# Thunder-Refix.net
KiCad netlist of a schematic drawn in Altium Designer
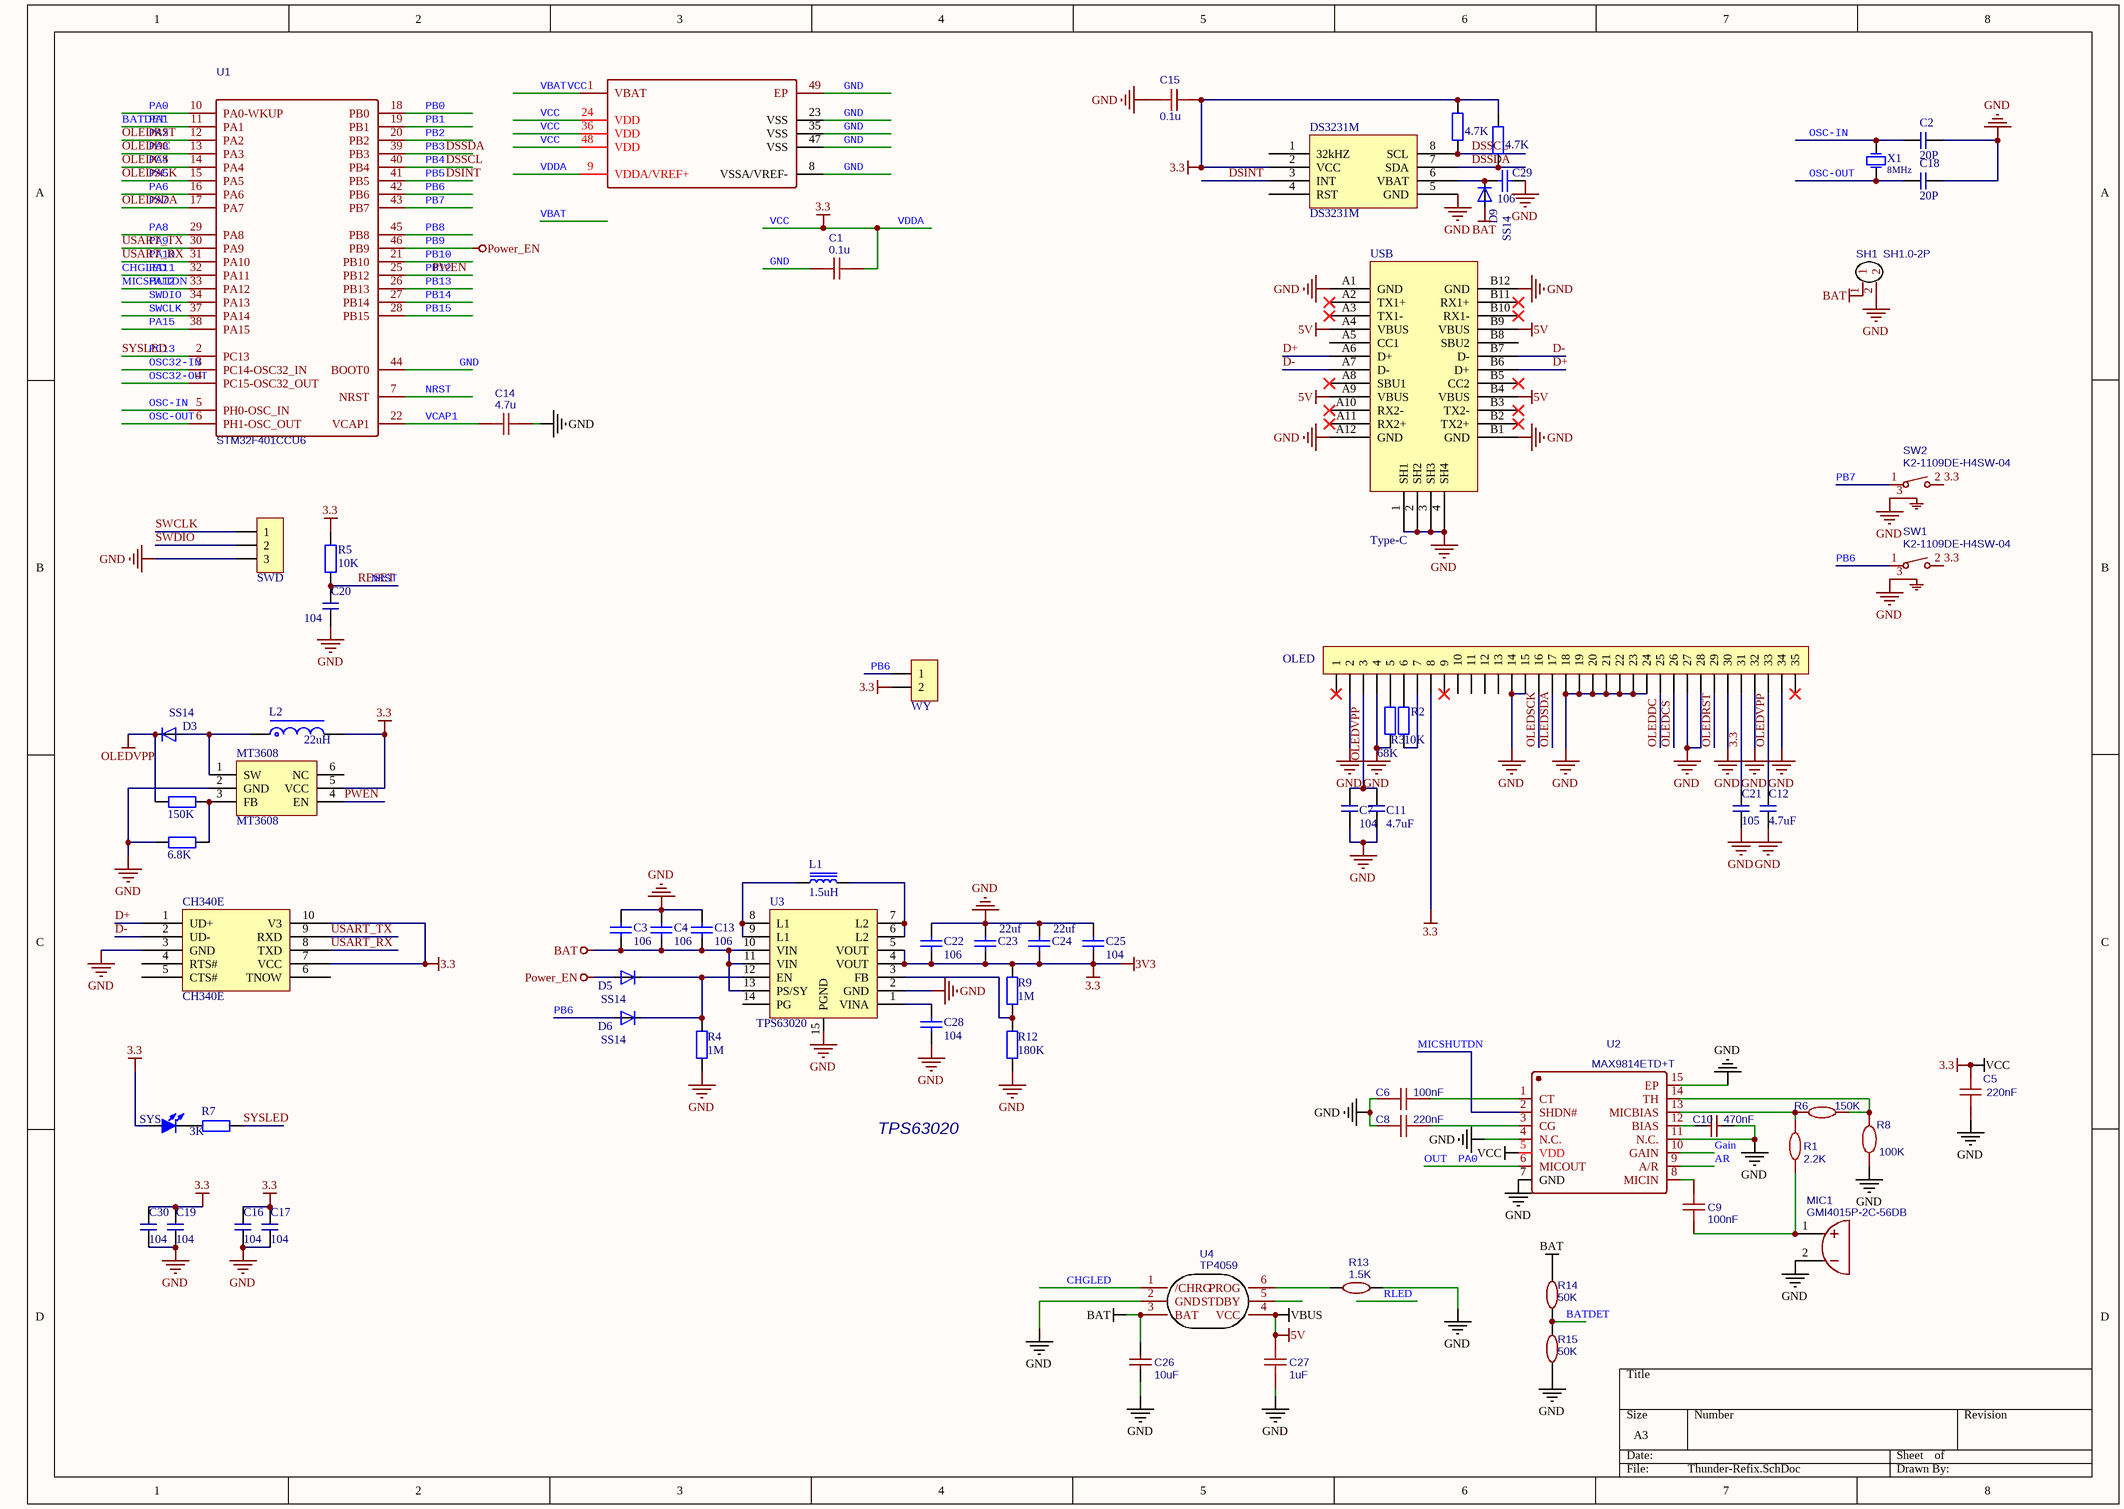
[diagram p0: Thunder-Refix.SchDoc]

(export (version "E")
  (design (tool "Eeschema 10.0.6"))
  (components
    (comp (ref "C1")
      (value "0.1u")
      (footprint "0603C")
      (fields (field (name "CONTRIBUTOR") "LCEDA_Lib"))
      (libsource (lib "altium-import") (part "root_2_0.1u_"))
    )
    (comp (ref "C2") (value "20P") (footprint "0603C") (libsource (lib "Schlib1") (part "电容")))
    (comp (ref "C3")
      (value "106")
      (footprint "我的PCB库:0603c")
      (fields (field (name "C") "106"))
      (libsource (lib "元件库") (part "cap"))
    )
    (comp (ref "C4")
      (value "106")
      (footprint "我的PCB库:0603c")
      (fields (field (name "C") "106"))
      (libsource (lib "元件库") (part "cap"))
    )
    (comp (ref "C5")
      (value "220nF")
      (footprint "0603c")
      (fields
        (field (name "BOM_SUPPLIER PART") "C354366")
        (field (name "BOM_MANUFACTURER PART") "GCJ21BR71H224KA01L")
        (field (name "CONTRIBUTOR") "LCSC")
      )
      (libsource (lib "altium-import") (part "root_1_220nF_"))
    )
    (comp (ref "C6")
      (value "100nF")
      (footprint "0603c")
      (fields
        (field (name "BOM_SUPPLIER PART") "C444732")
        (field (name "BOM_MANUFACTURER PART") "FS055C104K4Z2A")
        (field (name "CONTRIBUTOR") "LCSC")
      )
      (libsource (lib "altium-import") (part "root_1_100nF_"))
    )
    (comp (ref "C7") (value "104") (footprint "0603C") (libsource (lib "Schlib1") (part "电容")))
    (comp (ref "C8")
      (value "220nF")
      (footprint "0603c")
      (fields
        (field (name "BOM_SUPPLIER PART") "C354366")
        (field (name "BOM_MANUFACTURER PART") "GCJ21BR71H224KA01L")
        (field (name "CONTRIBUTOR") "LCSC")
      )
      (libsource (lib "altium-import") (part "root_0_220nF_"))
    )
    (comp (ref "C9")
      (value "100nF")
      (footprint "0603c")
      (fields
        (field (name "BOM_SUPPLIER PART") "C444732")
        (field (name "BOM_MANUFACTURER PART") "FS055C104K4Z2A")
        (field (name "CONTRIBUTOR") "LCSC")
      )
      (libsource (lib "altium-import") (part "root_0_100nF_"))
    )
    (comp (ref "C10")
      (value "470nF")
      (footprint "0603c")
      (fields
        (field (name "BOM_MANUFACTURER PART") "CL21B474KBFNNNE")
        (field (name "BOM_SUPPLIER PART") "C13967")
      )
      (libsource (lib "altium-import") (part "root_0_470nF_"))
    )
    (comp (ref "C11") (value "4.7uF") (footprint "0603C") (libsource (lib "Schlib1") (part "电容")))
    (comp (ref "C12") (value "4.7uF") (footprint "0603C") (libsource (lib "Schlib1") (part "电容")))
    (comp (ref "C13")
      (value "106")
      (footprint "0603c")
      (fields (field (name "C") "106"))
      (libsource (lib "元件库") (part "cap"))
    )
    (comp (ref "C14")
      (value "4.7u")
      (footprint "0603C")
      (fields (field (name "CONTRIBUTOR") "LCEDA_Lib"))
      (libsource (lib "altium-import") (part "root_0_4.7u_"))
    )
    (comp (ref "C15")
      (value "0.1u")
      (footprint "0603C")
      (fields (field (name "CONTRIBUTOR") "LCEDA_Lib"))
      (libsource (lib "altium-import") (part "root_2_0.1u_"))
    )
    (comp (ref "C16") (value "104") (footprint "0603C") (libsource (lib "Schlib1") (part "电容")))
    (comp (ref "C17") (value "104") (footprint "0603C") (libsource (lib "Schlib1") (part "电容")))
    (comp (ref "C18") (value "20P") (footprint "0603C") (libsource (lib "Schlib1") (part "电容")))
    (comp (ref "C19") (value "104") (footprint "0603C") (libsource (lib "Schlib1") (part "电容")))
    (comp (ref "C20") (value "104") (footprint "0603C") (libsource (lib "Schlib1") (part "电容")))
    (comp (ref "C21") (value "105") (footprint "0603C") (libsource (lib "Schlib1") (part "电容")))
    (comp (ref "C22")
      (value "106")
      (footprint "0603c")
      (fields (field (name "C") "106"))
      (libsource (lib "元件库") (part "cap"))
    )
    (comp (ref "C23")
      (value "22uf")
      (footprint "0603c")
      (fields (field (name "C") "22uf"))
      (libsource (lib "元件库") (part "cap"))
    )
    (comp (ref "C24")
      (value "22uf")
      (footprint "0603c")
      (fields (field (name "C") "22uf"))
      (libsource (lib "元件库") (part "cap"))
    )
    (comp (ref "C25")
      (value "104")
      (footprint "0603c")
      (fields (field (name "C") "104"))
      (libsource (lib "元件库") (part "cap"))
    )
    (comp (ref "C26")
      (value "10uF")
      (footprint "0603c")
      (fields
        (field (name "BOM_SUPPLIER PART") "C162317")
        (field (name "BOM_MANUFACTURER PART") "GRM21BB31C106KE15L")
        (field (name "CONTRIBUTOR") "LCSC")
      )
      (libsource (lib "altium-import") (part "root_1_10uF_"))
    )
    (comp (ref "C27")
      (value "1uF")
      (footprint "0603c")
      (fields
        (field (name "BOM_SUPPLIER PART") "C319195")
        (field (name "BOM_MANUFACTURER PART") "UMK212BJ105KG-T")
        (field (name "CONTRIBUTOR") "LCSC")
      )
      (libsource (lib "altium-import") (part "root_1_1uF_"))
    )
    (comp (ref "C28")
      (value "104")
      (footprint "0603c")
      (fields (field (name "C") "104"))
      (libsource (lib "元件库") (part "cap"))
    )
    (comp (ref "C29")
      (value "106")
      (footprint "0603c")
      (fields (field (name "C") "106"))
      (libsource (lib "元件库") (part "cap"))
    )
    (comp (ref "C30") (value "104") (footprint "0603C") (libsource (lib "Schlib1") (part "电容")))
    (comp (ref "CH340E") (value "CH340E") (footprint "MSOP10_L") (libsource (lib "CUBE_T1") (part "CH340E")))
    (comp (ref "D3")
      (value "SS14")
      (footprint "SOD323_1N4148WS")
      (description "Diode Switching 75V 0.3A 2-Pin SOD-323 T/R")
      (fields (field (name "MF") "ON Semiconductor") (field (name "MP") "1N4148WS"))
      (libsource (lib "1N4148WS") (part "1N4148WS"))
    )
    (comp (ref "D5")
      (value "SS14")
      (footprint "SOD323_1N4148WS")
      (description "Diode Switching 75V 0.3A 2-Pin SOD-323 T/R")
      (fields (field (name "MF") "ON Semiconductor") (field (name "MP") "1N4148WS"))
      (libsource (lib "1N4148WS") (part "1N4148WS"))
    )
    (comp (ref "D6")
      (value "SS14")
      (footprint "SOD323_1N4148WS")
      (description "Diode Switching 75V 0.3A 2-Pin SOD-323 T/R")
      (fields (field (name "MF") "ON Semiconductor") (field (name "MP") "1N4148WS"))
      (libsource (lib "1N4148WS") (part "1N4148WS"))
    )
    (comp (ref "D9")
      (value "SS14")
      (footprint "SOD323_1N4148WS")
      (description "Diode Switching 75V 0.3A 2-Pin SOD-323 T/R")
      (fields (field (name "MF") "ON Semiconductor") (field (name "MP") "1N4148WS"))
      (libsource (lib "1N4148WS") (part "1N4148WS"))
    )
    (comp (ref "DS3231M") (value "DS3231M") (footprint "SOP8") (libsource (lib "CUBE_T1") (part "DS3231M")))
    (comp (ref "L1")
      (value "1.5uH")
      (footprint "我的PCB库:IND-SMD_L3.0-W3.0_NR3010")
      (fields (field (name "_VALUE") "1.5uH"))
      (libsource (lib "元件库") (part "Inductor Iron 2"))
    )
    (comp (ref "L2")
      (value "22uH")
      (footprint "IND-SMD_L3.0-W3.0_NR3010")
      (description "功率屏蔽电感")
      (fields (field (name "版权归属") "源创客"))
      (libsource (lib "3.1   - 电阻-电容-电感") (part "L-CDRH"))
    )
    (comp (ref "MIC1")
      (value "GMI4015P-2C-56DB")
      (footprint "MIC-TH_BD4.0-P2.00-D0.4-L-FD")
      (fields
        (field (name "BOM_SUPPLIER PART") "C233299")
        (field (name "BOM_MANUFACTURER PART") "GMI4015P-2C-56db")
        (field (name "CONTRIBUTOR") "LCSC")
      )
      (libsource (lib "altium-import") (part "root_0_GMI4015P-2C-56DB_"))
    )
    (comp (ref "MT3608")
      (value "MT3608")
      (footprint "SOT23-6N")
      (description "可调升压芯片")
      (fields (field (name "版权归属") "源创客"))
      (libsource (lib "1.3   - 电源类芯片") (part "SX1308"))
    )
    (comp (ref "OLED")
      (value "FPC1.0-35P")
      (footprint "1.69 OLED")
      (description "FPC连接器")
      (fields (field (name "版权归属") "源创客"))
      (libsource (lib "4.14 - FPC连接器") (part "FPC-35P"))
    )
    (comp (ref "R1")
      (value "2.2K")
      (footprint "0603r")
      (fields
        (field (name "BOM_SUPPLIER PART") "C325769")
        (field (name "BOM_MANUFACTURER PART") "RMC08052.2K1%N")
        (field (name "CONTRIBUTOR") "LCSC")
      )
      (libsource (lib "altium-import") (part "root_1_2.2K_"))
    )
    (comp (ref "R2")
      (value "10K")
      (footprint "0603R")
      (description "贴片电阻")
      (fields (field (name "版权归属") "源创客"))
      (libsource (lib "3.1   - 电阻-电容-电感") (part "R"))
    )
    (comp (ref "R3")
      (value "68K")
      (footprint "0603R")
      (description "贴片电阻")
      (fields (field (name "版权归属") "源创客"))
      (libsource (lib "3.1   - 电阻-电容-电感") (part "R"))
    )
    (comp (ref "R4")
      (value "1M")
      (footprint "0603r")
      (fields (field (name "R") "1M"))
      (libsource (lib "元件库") (part "Res"))
    )
    (comp (ref "R5")
      (value "10K")
      (footprint "0603R")
      (description "贴片电阻")
      (fields (field (name "版权归属") "源创客"))
      (libsource (lib "3.1   - 电阻-电容-电感") (part "R"))
    )
    (comp (ref "R6")
      (value "150K")
      (footprint "0603r")
      (fields
        (field (name "BOM_SUPPLIER PART") "C325765")
        (field (name "BOM_MANUFACTURER PART") "RMC0805150K1%N")
        (field (name "CONTRIBUTOR") "LCSC")
      )
      (libsource (lib "altium-import") (part "root_0_150K_"))
    )
    (comp (ref "R7")
      (value "3K")
      (footprint "0603R")
      (description "贴片电阻")
      (fields (field (name "版权归属") "源创客"))
      (libsource (lib "3.1   - 电阻-电容-电感") (part "R"))
    )
    (comp (ref "R8")
      (value "100K")
      (footprint "0603r")
      (fields
        (field (name "BOM_SUPPLIER PART") "C346756")
        (field (name "BOM_MANUFACTURER PART") "RTAN0805BKE100K")
        (field (name "CONTRIBUTOR") "LCSC")
      )
      (libsource (lib "altium-import") (part "root_1_100K_"))
    )
    (comp (ref "R9")
      (value "1M")
      (footprint "0603r")
      (fields (field (name "R") "1M"))
      (libsource (lib "元件库") (part "Res"))
    )
    (comp (ref "R10")
      (value "4.7K")
      (footprint "0603R")
      (description "贴片电阻")
      (fields (field (name "版权归属") "源创客"))
      (libsource (lib "3.1   - 电阻-电容-电感") (part "R"))
    )
    (comp (ref "R11")
      (value "4.7K")
      (footprint "0603R")
      (description "贴片电阻")
      (fields (field (name "版权归属") "源创客"))
      (libsource (lib "3.1   - 电阻-电容-电感") (part "R"))
    )
    (comp (ref "R12")
      (value "180K")
      (footprint "0603r")
      (fields (field (name "R") "180K"))
      (libsource (lib "元件库") (part "Res"))
    )
    (comp (ref "R13")
      (value "1.5K")
      (footprint "0603r")
      (fields
        (field (name "BOM_MANUFACTURER PART") "RC0603FR-071K5L")
        (field (name "BOM_SUPPLIER PART") "C114668")
      )
      (libsource (lib "altium-import") (part "root_0_1.5K_"))
    )
    (comp (ref "R14")
      (value "50K")
      (footprint "0603r")
      (fields
        (field (name "BOM_MANUFACTURER PART") "RC0603FR-071K5L")
        (field (name "BOM_SUPPLIER PART") "C114668")
      )
      (libsource (lib "altium-import") (part "root_1_1.5K_"))
    )
    (comp (ref "R15")
      (value "50K")
      (footprint "0603r")
      (fields
        (field (name "BOM_MANUFACTURER PART") "RC0603FR-071K5L")
        (field (name "BOM_SUPPLIER PART") "C114668")
      )
      (libsource (lib "altium-import") (part "root_1_1.5K_"))
    )
    (comp (ref "RB")
      (value "150K")
      (footprint "0603R")
      (description "贴片电阻")
      (fields (field (name "版权归属") "源创客"))
      (libsource (lib "3.1   - 电阻-电容-电感") (part "R"))
    )
    (comp (ref "RS")
      (value "6.8K")
      (footprint "0603R")
      (description "贴片电阻")
      (fields (field (name "版权归属") "源创客"))
      (libsource (lib "3.1   - 电阻-电容-电感") (part "R"))
    )
    (comp (ref "SH1")
      (value "SH1.0-2P")
      (footprint "SH1.0-2P")
      (fields (field (name "CONTRIBUTOR") "perry2867"))
      (libsource (lib "altium-import") (part "root_1_SH1.0-2P_"))
    )
    (comp (ref "SW1")
      (value "K2-1109DE-H4SW-04")
      (footprint "KEY-TH_K2-1109DE-CXXW-XX")
      (fields (field (name "BOM_SUPPLIER PART") "C961730") (field (name "CONTRIBUTOR") "LCSC"))
      (libsource (lib "altium-import") (part "root_0_K2-1109DE-H4SW-04_"))
    )
    (comp (ref "SW2")
      (value "K2-1109DE-H4SW-04")
      (footprint "KEY-TH_K2-1109DE-CXXW-XX")
      (fields (field (name "BOM_SUPPLIER PART") "C961730") (field (name "CONTRIBUTOR") "LCSC"))
      (libsource (lib "altium-import") (part "root_0_K2-1109DE-H4SW-04_"))
    )
    (comp (ref "SWD")
      (value "HDR-1X3")
      (footprint "ZH1.5-LI-3P")
      (description "3P接插件")
      (fields (field (name "版权归属") "源创客"))
      (libsource (lib "4.3   - 接插件-脚距1.5") (part "Header 3"))
    )
    (comp (ref "SYS")
      (value "粉色")
      (footprint "0603LED")
      (description "方形LED")
      (fields (field (name "版权归属") "源创客"))
      (libsource (lib "9.1   - LED") (part "LED-F234"))
    )
    (comp (ref "U1")
      (value "STM32F401CCU6")
      (footprint "QFN48 7X7_N")
      (fields (field (name "BOM_SUPPLIER PART") "C79861") (field (name "SUBPART_NO") "1"))
      (libsource (lib "Galaxy") (part "STM32F401CCU6"))
    )
    (comp (ref "U2")
      (value "MAX9814ETD+T")
      (footprint "TDFN-14_L3.0-W3.0-P0.40-BL-EP")
      (fields (field (name "BOM_SUPPLIER PART") "C41714"))
      (libsource (lib "altium-import") (part "root_0_MAX9814ETD+T_"))
    )
    (comp (ref "U3")
      (value "TPS63020")
      (footprint "我的PCB库:TPS63020")
      (libsource (lib "我的元件库") (part "TPS63020"))
    )
    (comp (ref "U4")
      (value "TP4059")
      (footprint "SOT23-6N")
      (fields (field (name "BOM_SUPPLIER PART") "C80364"))
      (libsource (lib "altium-import") (part "root_0_TP4059_"))
    )
    (comp (ref "USB") (value "Type-C") (footprint "Type-C") (libsource (lib "元件") (part "Type-C")))
    (comp (ref "WY")
      (value "HDR-1X2")
      (footprint "MX 1.25-WI-2P")
      (description "2P接插件")
      (fields (field (name "版权归属") "源创客"))
      (libsource (lib "4.2   - 接插件-脚距1.25") (part "Header 2"))
    )
    (comp (ref "X1")
      (value "8MHz")
      (footprint "OSC 5032-2P")
      (description "XTAL,8MHz,±20PPM,12.6*4.5")
      (fields (field (name "Comment") "1.6.1.01.005.001"))
      (libsource (lib "Mark_7") (part "1.6.1.01.005.001"))
    )
  )
  (nets
    (net (code "1") (name "/AR") (class "Default")
      (node (ref "U2") (pin "9") (pinfunction "A/R_9") (pintype "passive"))
    )
    (net (code "2") (name "/BATDET") (class "Default")
      (node (ref "R14") (pin "1") (pinfunction "1_1") (pintype "passive"))
      (node (ref "R15") (pin "2") (pinfunction "2_2") (pintype "passive"))
      (node (ref "U1") (pin "11") (pinfunction "PA1_11") (pintype "passive"))
    )
    (net (code "3") (name "/CHGLED") (class "Default")
      (node (ref "U1") (pin "32") (pinfunction "PA11_32") (pintype "passive"))
      (node (ref "U4") (pin "1") (pinfunction "/CHRG_1") (pintype "passive"))
    )
    (net (code "4") (name "/D+") (class "Default")
      (node (ref "CH340E") (pin "1") (pinfunction "UD+_1") (pintype "passive"))
      (node (ref "USB") (pin "A6") (pinfunction "D+_A6") (pintype "passive"))
      (node (ref "USB") (pin "B6") (pinfunction "D+_B6") (pintype "passive"))
    )
    (net (code "5") (name "/D-") (class "Default")
      (node (ref "CH340E") (pin "2") (pinfunction "UD-_2") (pintype "passive"))
      (node (ref "USB") (pin "A7") (pinfunction "D-_A7") (pintype "passive"))
      (node (ref "USB") (pin "B7") (pinfunction "D-_B7") (pintype "passive"))
    )
    (net (code "6") (name "/DSINT") (class "Default")
      (node (ref "DS3231M") (pin "3") (pinfunction "INT_3") (pintype "passive"))
      (node (ref "U1") (pin "41") (pinfunction "PB5_41") (pintype "passive"))
    )
    (net (code "7") (name "/DSSCL") (class "Default")
      (node (ref "DS3231M") (pin "8") (pinfunction "SCL_8") (pintype "passive"))
      (node (ref "R10") (pin "2") (pinfunction "2_2") (pintype "passive"))
      (node (ref "U1") (pin "40") (pinfunction "PB4_40") (pintype "passive"))
    )
    (net (code "8") (name "/DSSDA") (class "Default")
      (node (ref "DS3231M") (pin "7") (pinfunction "SDA_7") (pintype "passive"))
      (node (ref "R11") (pin "2") (pinfunction "2_2") (pintype "passive"))
      (node (ref "U1") (pin "39") (pinfunction "PB3_39") (pintype "passive"))
    )
    (net (code "9") (name "/Gain") (class "Default")
      (node (ref "U2") (pin "10") (pinfunction "GAIN_10") (pintype "passive"))
    )
    (net (code "10") (name "/MICSHUTDN") (class "Default")
      (node (ref "U1") (pin "33") (pinfunction "PA12_33") (pintype "passive"))
      (node (ref "U2") (pin "2") (pinfunction "SHDN#_2") (pintype "passive"))
    )
    (net (code "11") (name "/NRST") (class "Default")
      (node (ref "C20") (pin "1") (pinfunction "1_1") (pintype "passive"))
      (node (ref "R5") (pin "2") (pinfunction "2_2") (pintype "passive"))
      (node (ref "U1") (pin "7") (pinfunction "NRST_7") (pintype "passive"))
    )
    (net (code "12") (name "/OLEDCS") (class "Default")
      (node (ref "OLED") (pin "26") (pinfunction "26_26") (pintype "passive"))
      (node (ref "U1") (pin "14") (pinfunction "PA4_14") (pintype "passive"))
    )
    (net (code "13") (name "/OLEDDC") (class "Default")
      (node (ref "OLED") (pin "25") (pinfunction "25_25") (pintype "passive"))
      (node (ref "U1") (pin "13") (pinfunction "PA3_13") (pintype "passive"))
    )
    (net (code "14") (name "/OLEDRST") (class "Default")
      (node (ref "OLED") (pin "29") (pinfunction "29_29") (pintype "passive"))
      (node (ref "U1") (pin "12") (pinfunction "PA2_12") (pintype "passive"))
    )
    (net (code "15") (name "/OLEDSCK") (class "Default")
      (node (ref "OLED") (pin "16") (pinfunction "16_16") (pintype "passive"))
      (node (ref "U1") (pin "15") (pinfunction "PA5_15") (pintype "passive"))
    )
    (net (code "16") (name "/OLEDSDA") (class "Default")
      (node (ref "OLED") (pin "17") (pinfunction "17_17") (pintype "passive"))
      (node (ref "U1") (pin "17") (pinfunction "PA7_17") (pintype "passive"))
    )
    (net (code "17") (name "/OSC-IN") (class "Default")
      (node (ref "C2") (pin "2") (pinfunction "2_2") (pintype "passive"))
      (node (ref "U1") (pin "5") (pinfunction "PH0-OSC_IN_5") (pintype "passive"))
      (node (ref "X1") (pin "1") (pinfunction "OSC1_1") (pintype "passive"))
    )
    (net (code "18") (name "/OSC-OUT") (class "Default")
      (node (ref "C18") (pin "2") (pinfunction "2_2") (pintype "passive"))
      (node (ref "U1") (pin "6") (pinfunction "PH1-OSC_OUT_6") (pintype "passive"))
      (node (ref "X1") (pin "2") (pinfunction "OSC2_2") (pintype "passive"))
    )
    (net (code "19") (name "/OSC32-IN") (class "Default")
      (node (ref "U1") (pin "3") (pinfunction "PC14-OSC32_IN_3") (pintype "passive"))
    )
    (net (code "20") (name "/OSC32-OUT") (class "Default")
      (node (ref "U1") (pin "4") (pinfunction "PC15-OSC32_OUT_4") (pintype "passive"))
    )
    (net (code "21") (name "/OUT") (class "Default")
      (node (ref "U1") (pin "10") (pinfunction "PA0-WKUP_10") (pintype "passive"))
      (node (ref "U2") (pin "6") (pinfunction "MICOUT_6") (pintype "passive"))
    )
    (net (code "22") (name "/PA6") (class "Default")
      (node (ref "U1") (pin "16") (pinfunction "PA6_16") (pintype "passive"))
    )
    (net (code "23") (name "/PA8") (class "Default")
      (node (ref "U1") (pin "29") (pinfunction "PA8_29") (pintype "passive"))
    )
    (net (code "24") (name "/PA9") (class "Default")
      (node (ref "CH340E") (pin "9") (pinfunction "RXD_9") (pintype "passive"))
      (node (ref "U1") (pin "30") (pinfunction "PA9_30") (pintype "passive"))
    )
    (net (code "25") (name "/PA10") (class "Default")
      (node (ref "CH340E") (pin "8") (pinfunction "TXD_8") (pintype "passive"))
      (node (ref "U1") (pin "31") (pinfunction "PA10_31") (pintype "passive"))
    )
    (net (code "26") (name "/PA15") (class "Default")
      (node (ref "U1") (pin "38") (pinfunction "PA15_38") (pintype "passive"))
    )
    (net (code "27") (name "/PB0") (class "Default")
      (node (ref "U1") (pin "18") (pinfunction "PB0_18") (pintype "passive"))
    )
    (net (code "28") (name "/PB1") (class "Default")
      (node (ref "U1") (pin "19") (pinfunction "PB1_19") (pintype "passive"))
    )
    (net (code "29") (name "/PB2") (class "Default")
      (node (ref "U1") (pin "20") (pinfunction "PB2_20") (pintype "passive"))
    )
    (net (code "30") (name "/PB6") (class "Default")
      (node (ref "D6") (pin "A") (pinfunction "A_A") (pintype "passive"))
      (node (ref "SW1") (pin "1") (pinfunction "1_1") (pintype "passive"))
      (node (ref "U1") (pin "42") (pinfunction "PB6_42") (pintype "passive"))
      (node (ref "WY") (pin "1") (pinfunction "1_1") (pintype "passive"))
    )
    (net (code "31") (name "/PB7") (class "Default")
      (node (ref "SW2") (pin "1") (pinfunction "1_1") (pintype "passive"))
      (node (ref "U1") (pin "43") (pinfunction "PB7_43") (pintype "passive"))
    )
    (net (code "32") (name "/PB8") (class "Default")
      (node (ref "U1") (pin "45") (pinfunction "PB8_45") (pintype "passive"))
    )
    (net (code "33") (name "/PB10") (class "Default")
      (node (ref "U1") (pin "21") (pinfunction "PB10_21") (pintype "passive"))
    )
    (net (code "34") (name "/PB12") (class "Default")
      (node (ref "MT3608") (pin "4") (pinfunction "EN_4") (pintype "passive"))
      (node (ref "U1") (pin "25") (pinfunction "PB12_25") (pintype "passive"))
    )
    (net (code "35") (name "/PB13") (class "Default")
      (node (ref "U1") (pin "26") (pinfunction "PB13_26") (pintype "passive"))
    )
    (net (code "36") (name "/PB14") (class "Default")
      (node (ref "U1") (pin "27") (pinfunction "PB14_27") (pintype "passive"))
    )
    (net (code "37") (name "/PB15") (class "Default")
      (node (ref "U1") (pin "28") (pinfunction "PB15_28") (pintype "passive"))
    )
    (net (code "38") (name "/PC13") (class "Default")
      (node (ref "R7") (pin "1") (pinfunction "1_1") (pintype "passive"))
      (node (ref "U1") (pin "2") (pinfunction "PC13_2") (pintype "passive"))
    )
    (net (code "40") (name "/SWCLK") (class "Default")
      (node (ref "SWD") (pin "1") (pinfunction "1_1") (pintype "passive"))
      (node (ref "U1") (pin "37") (pinfunction "PA14_37") (pintype "passive"))
    )
    (net (code "41") (name "/SWDIO") (class "Default")
      (node (ref "SWD") (pin "2") (pinfunction "2_2") (pintype "passive"))
      (node (ref "U1") (pin "34") (pinfunction "PA13_34") (pintype "passive"))
    )
    (net (code "42") (name "/VCAP1") (class "Default")
      (node (ref "C14") (pin "1") (pinfunction "1_1") (pintype "passive"))
      (node (ref "U1") (pin "22") (pinfunction "VCAP1_22") (pintype "passive"))
    )
    (net (code "43") (name "3.3") (class "Default")
      (node (ref "C1") (pin "1") (pinfunction "1_1") (pintype "passive"))
      (node (ref "C15") (pin "1") (pinfunction "1_1") (pintype "passive"))
      (node (ref "C16") (pin "1") (pinfunction "1_1") (pintype "passive"))
      (node (ref "C17") (pin "1") (pinfunction "1_1") (pintype "passive"))
      (node (ref "C19") (pin "1") (pinfunction "1_1") (pintype "passive"))
      (node (ref "C21") (pin "1") (pinfunction "1_1") (pintype "passive"))
      (node (ref "C22") (pin "1") (pinfunction "1_1") (pintype "passive"))
      (node (ref "C23") (pin "1") (pinfunction "1_1") (pintype "passive"))
      (node (ref "C24") (pin "1") (pinfunction "1_1") (pintype "passive"))
      (node (ref "C25") (pin "1") (pinfunction "1_1") (pintype "passive"))
      (node (ref "C30") (pin "1") (pinfunction "1_1") (pintype "passive"))
      (node (ref "C5") (pin "2") (pinfunction "2_2") (pintype "passive"))
      (node (ref "CH340E") (pin "10") (pinfunction "V3_10") (pintype "passive"))
      (node (ref "CH340E") (pin "7") (pinfunction "VCC_7") (pintype "passive"))
      (node (ref "DS3231M") (pin "2") (pinfunction "VCC_2") (pintype "passive"))
      (node (ref "L2") (pin "2") (pinfunction "2_2") (pintype "passive"))
      (node (ref "MT3608") (pin "5") (pinfunction "VCC_5") (pintype "passive"))
      (node (ref "OLED") (pin "31") (pinfunction "31_31") (pintype "passive"))
      (node (ref "OLED") (pin "8") (pinfunction "8_8") (pintype "passive"))
      (node (ref "R10") (pin "1") (pinfunction "1_1") (pintype "passive"))
      (node (ref "R11") (pin "1") (pinfunction "1_1") (pintype "passive"))
      (node (ref "R5") (pin "1") (pinfunction "1_1") (pintype "passive"))
      (node (ref "R9") (pin "1") (pinfunction "1_1") (pintype "passive"))
      (node (ref "SW1") (pin "2") (pinfunction "2_2") (pintype "passive"))
      (node (ref "SW2") (pin "2") (pinfunction "2_2") (pintype "passive"))
      (node (ref "SYS") (pin "1") (pinfunction "A_1") (pintype "passive"))
      (node (ref "U1") (pin "1") (pinfunction "VBAT_1") (pintype "passive"))
      (node (ref "U1") (pin "24") (pinfunction "VDD_24") (pintype "passive"))
      (node (ref "U1") (pin "36") (pinfunction "VDD_36") (pintype "passive"))
      (node (ref "U1") (pin "48") (pinfunction "VDD_48") (pintype "passive"))
      (node (ref "U1") (pin "9") (pinfunction "VDDA/VREF+_9") (pintype "passive"))
      (node (ref "U2") (pin "5") (pinfunction "VDD_5") (pintype "passive"))
      (node (ref "U3") (pin "4") (pinfunction "VOUT_4") (pintype "passive"))
      (node (ref "U3") (pin "5") (pinfunction "VOUT_5") (pintype "passive"))
      (node (ref "WY") (pin "2") (pinfunction "2_2") (pintype "passive"))
    )
    (net (code "44") (name "5V") (class "Default")
      (node (ref "C27") (pin "1") (pinfunction "1_1") (pintype "passive"))
      (node (ref "U4") (pin "4") (pinfunction "VCC_4") (pintype "passive"))
      (node (ref "USB") (pin "A4") (pinfunction "VBUS_A4") (pintype "passive"))
      (node (ref "USB") (pin "A9") (pinfunction "VBUS_A9") (pintype "passive"))
      (node (ref "USB") (pin "B4") (pinfunction "VBUS_B4") (pintype "passive"))
      (node (ref "USB") (pin "B9") (pinfunction "VBUS_B9") (pintype "passive"))
    )
    (net (code "45") (name "BAT") (class "Default")
      (node (ref "C13") (pin "1") (pinfunction "1_1") (pintype "passive"))
      (node (ref "C26") (pin "2") (pinfunction "2_2") (pintype "passive"))
      (node (ref "C3") (pin "1") (pinfunction "1_1") (pintype "passive"))
      (node (ref "C4") (pin "1") (pinfunction "1_1") (pintype "passive"))
      (node (ref "D9") (pin "A") (pinfunction "A_A") (pintype "passive"))
      (node (ref "R14") (pin "2") (pinfunction "2_2") (pintype "passive"))
      (node (ref "SH1") (pin "1") (pinfunction "1_1") (pintype "passive"))
      (node (ref "U3") (pin "10") (pinfunction "VIN_10") (pintype "passive"))
      (node (ref "U3") (pin "11") (pinfunction "VIN_11") (pintype "passive"))
      (node (ref "U3") (pin "13") (pinfunction "PS/SY_13") (pintype "passive"))
      (node (ref "U4") (pin "3") (pinfunction "BAT_3") (pintype "passive"))
    )
    (net (code "46") (name "GND") (class "Default")
      (node (ref "C1") (pin "2") (pinfunction "2_2") (pintype "passive"))
      (node (ref "C10") (pin "2") (pinfunction "2_2") (pintype "passive"))
      (node (ref "C11") (pin "2") (pinfunction "2_2") (pintype "passive"))
      (node (ref "C12") (pin "2") (pinfunction "2_2") (pintype "passive"))
      (node (ref "C13") (pin "2") (pinfunction "2_2") (pintype "passive"))
      (node (ref "C14") (pin "2") (pinfunction "2_2") (pintype "passive"))
      (node (ref "C15") (pin "2") (pinfunction "2_2") (pintype "passive"))
      (node (ref "C16") (pin "2") (pinfunction "2_2") (pintype "passive"))
      (node (ref "C17") (pin "2") (pinfunction "2_2") (pintype "passive"))
      (node (ref "C18") (pin "1") (pinfunction "1_1") (pintype "passive"))
      (node (ref "C19") (pin "2") (pinfunction "2_2") (pintype "passive"))
      (node (ref "C2") (pin "1") (pinfunction "1_1") (pintype "passive"))
      (node (ref "C20") (pin "2") (pinfunction "2_2") (pintype "passive"))
      (node (ref "C21") (pin "2") (pinfunction "2_2") (pintype "passive"))
      (node (ref "C22") (pin "2") (pinfunction "2_2") (pintype "passive"))
      (node (ref "C23") (pin "2") (pinfunction "2_2") (pintype "passive"))
      (node (ref "C24") (pin "2") (pinfunction "2_2") (pintype "passive"))
      (node (ref "C25") (pin "2") (pinfunction "2_2") (pintype "passive"))
      (node (ref "C26") (pin "1") (pinfunction "1_1") (pintype "passive"))
      (node (ref "C27") (pin "2") (pinfunction "2_2") (pintype "passive"))
      (node (ref "C28") (pin "1") (pinfunction "1_1") (pintype "passive"))
      (node (ref "C29") (pin "1") (pinfunction "1_1") (pintype "passive"))
      (node (ref "C3") (pin "2") (pinfunction "2_2") (pintype "passive"))
      (node (ref "C30") (pin "2") (pinfunction "2_2") (pintype "passive"))
      (node (ref "C4") (pin "2") (pinfunction "2_2") (pintype "passive"))
      (node (ref "C5") (pin "1") (pinfunction "1_1") (pintype "passive"))
      (node (ref "C6") (pin "1") (pinfunction "1_1") (pintype "passive"))
      (node (ref "C7") (pin "2") (pinfunction "2_2") (pintype "passive"))
      (node (ref "C8") (pin "1") (pinfunction "1_1") (pintype "passive"))
      (node (ref "CH340E") (pin "3") (pinfunction "GND_3") (pintype "passive"))
      (node (ref "DS3231M") (pin "5") (pinfunction "GND_5") (pintype "passive"))
      (node (ref "MIC1") (pin "2") (pinfunction "2_2") (pintype "passive"))
      (node (ref "MT3608") (pin "2") (pinfunction "GND_2") (pintype "passive"))
      (node (ref "OLED") (pin "14") (pinfunction "14_14") (pintype "passive"))
      (node (ref "OLED") (pin "15") (pinfunction "15_15") (pintype "passive"))
      (node (ref "OLED") (pin "18") (pinfunction "18_18") (pintype "passive"))
      (node (ref "OLED") (pin "19") (pinfunction "19_19") (pintype "passive"))
      (node (ref "OLED") (pin "2") (pinfunction "2_2") (pintype "passive"))
      (node (ref "OLED") (pin "20") (pinfunction "20_20") (pintype "passive"))
      (node (ref "OLED") (pin "21") (pinfunction "21_21") (pintype "passive"))
      (node (ref "OLED") (pin "22") (pinfunction "22_22") (pintype "passive"))
      (node (ref "OLED") (pin "23") (pinfunction "23_23") (pintype "passive"))
      (node (ref "OLED") (pin "24") (pinfunction "24_24") (pintype "passive"))
      (node (ref "OLED") (pin "27") (pinfunction "27_27") (pintype "passive"))
      (node (ref "OLED") (pin "28") (pinfunction "28_28") (pintype "passive"))
      (node (ref "OLED") (pin "30") (pinfunction "30_30") (pintype "passive"))
      (node (ref "OLED") (pin "32") (pinfunction "32_32") (pintype "passive"))
      (node (ref "OLED") (pin "34") (pinfunction "34_34") (pintype "passive"))
      (node (ref "OLED") (pin "4") (pinfunction "4_4") (pintype "passive"))
      (node (ref "R12") (pin "2") (pinfunction "2_2") (pintype "passive"))
      (node (ref "R13") (pin "2") (pinfunction "2_2") (pintype "passive"))
      (node (ref "R15") (pin "1") (pinfunction "1_1") (pintype "passive"))
      (node (ref "R3") (pin "1") (pinfunction "1_1") (pintype "passive"))
      (node (ref "R4") (pin "2") (pinfunction "2_2") (pintype "passive"))
      (node (ref "R8") (pin "1") (pinfunction "1_1") (pintype "passive"))
      (node (ref "RS") (pin "1") (pinfunction "1_1") (pintype "passive"))
      (node (ref "SH1") (pin "2") (pinfunction "2_2") (pintype "passive"))
      (node (ref "SW1") (pin "3") (pinfunction "GND_3") (pintype "passive"))
      (node (ref "SW2") (pin "3") (pinfunction "GND_3") (pintype "passive"))
      (node (ref "SWD") (pin "3") (pinfunction "3_3") (pintype "passive"))
      (node (ref "U1") (pin "23") (pinfunction "VSS_23") (pintype "passive"))
      (node (ref "U1") (pin "35") (pinfunction "VSS_35") (pintype "passive"))
      (node (ref "U1") (pin "44") (pinfunction "BOOT0_44") (pintype "passive"))
      (node (ref "U1") (pin "47") (pinfunction "VSS_47") (pintype "passive"))
      (node (ref "U1") (pin "49") (pinfunction "EP_49") (pintype "passive"))
      (node (ref "U1") (pin "8") (pinfunction "VSSA/VREF-_8") (pintype "passive"))
      (node (ref "U2") (pin "11") (pinfunction "N.C._11") (pintype "passive"))
      (node (ref "U2") (pin "15") (pinfunction "EP_15") (pintype "passive"))
      (node (ref "U2") (pin "4") (pinfunction "N.C._4") (pintype "passive"))
      (node (ref "U2") (pin "7") (pinfunction "GND_7") (pintype "passive"))
      (node (ref "U3") (pin "15") (pinfunction "PGND_15") (pintype "passive"))
      (node (ref "U3") (pin "2") (pinfunction "GND_2") (pintype "passive"))
      (node (ref "U4") (pin "2") (pinfunction "GND_2") (pintype "passive"))
      (node (ref "USB") (pin "1") (pinfunction "SH1_1") (pintype "passive"))
      (node (ref "USB") (pin "2") (pinfunction "SH2_2") (pintype "passive"))
      (node (ref "USB") (pin "3") (pinfunction "SH3_3") (pintype "passive"))
      (node (ref "USB") (pin "4") (pinfunction "SH4_4") (pintype "passive"))
      (node (ref "USB") (pin "A1") (pinfunction "GND_A1") (pintype "passive"))
      (node (ref "USB") (pin "A12") (pinfunction "GND_A12") (pintype "passive"))
      (node (ref "USB") (pin "B1") (pinfunction "GND_B1") (pintype "passive"))
      (node (ref "USB") (pin "B12") (pinfunction "GND_B12") (pintype "passive"))
    )
    (net (code "47") (name "Net-(C9-Pad2)") (class "Default")
      (node (ref "C9") (pin "2") (pinfunction "2_2") (pintype "passive"))
      (node (ref "MIC1") (pin "1") (pinfunction "1_1") (pintype "passive"))
      (node (ref "R1") (pin "1") (pinfunction "1_1") (pintype "passive"))
    )
    (net (code "48") (name "Net-(DS3231M-VBAT)") (class "Default")
      (node (ref "C29") (pin "2") (pinfunction "2_2") (pintype "passive"))
      (node (ref "D9") (pin "C") (pinfunction "C_C") (pintype "passive"))
      (node (ref "DS3231M") (pin "6") (pinfunction "VBAT_6") (pintype "passive"))
    )
    (net (code "49") (name "Net-(L1-Pad1)") (class "Default")
      (node (ref "L1") (pin "1") (pinfunction "1_1") (pintype "passive"))
      (node (ref "U3") (pin "8") (pinfunction "L1_8") (pintype "passive"))
      (node (ref "U3") (pin "9") (pinfunction "L1_9") (pintype "passive"))
    )
    (net (code "50") (name "Net-(L1-Pad2)") (class "Default")
      (node (ref "L1") (pin "2") (pinfunction "2_2") (pintype "passive"))
      (node (ref "U3") (pin "6") (pinfunction "L2_6") (pintype "passive"))
      (node (ref "U3") (pin "7") (pinfunction "L2_7") (pintype "passive"))
    )
    (net (code "51") (name "Net-(MT3608-FB)") (class "Default")
      (node (ref "MT3608") (pin "3") (pinfunction "FB_3") (pintype "passive"))
      (node (ref "RB") (pin "2") (pinfunction "2_2") (pintype "passive"))
      (node (ref "RS") (pin "2") (pinfunction "2_2") (pintype "passive"))
    )
    (net (code "52") (name "Net-(MT3608-SW)") (class "Default")
      (node (ref "D3") (pin "A") (pinfunction "A_A") (pintype "passive"))
      (node (ref "L2") (pin "1") (pinfunction "1_1") (pintype "passive"))
      (node (ref "MT3608") (pin "1") (pinfunction "SW_1") (pintype "passive"))
    )
    (net (code "53") (name "Net-(OLED-Pad5)") (class "Default")
      (node (ref "OLED") (pin "5") (pinfunction "5_5") (pintype "passive"))
      (node (ref "R3") (pin "2") (pinfunction "2_2") (pintype "passive"))
    )
    (net (code "54") (name "Net-(OLED-Pad6)") (class "Default")
      (node (ref "OLED") (pin "6") (pinfunction "6_6") (pintype "passive"))
      (node (ref "R2") (pin "2") (pinfunction "2_2") (pintype "passive"))
    )
    (net (code "55") (name "Net-(OLED-Pad7)") (class "Default")
      (node (ref "OLED") (pin "7") (pinfunction "7_7") (pintype "passive"))
      (node (ref "R2") (pin "1") (pinfunction "1_1") (pintype "passive"))
    )
    (net (code "56") (name "Net-(SYS-K)") (class "Default")
      (node (ref "R7") (pin "2") (pinfunction "2_2") (pintype "passive"))
      (node (ref "SYS") (pin "2") (pinfunction "K_2") (pintype "passive"))
    )
    (net (code "57") (name "Net-(U2-BIAS)") (class "Default")
      (node (ref "C10") (pin "1") (pinfunction "1_1") (pintype "passive"))
      (node (ref "U2") (pin "12") (pinfunction "BIAS_12") (pintype "passive"))
    )
    (net (code "58") (name "Net-(U2-CG)") (class "Default")
      (node (ref "C8") (pin "2") (pinfunction "2_2") (pintype "passive"))
      (node (ref "U2") (pin "3") (pinfunction "CG_3") (pintype "passive"))
    )
    (net (code "59") (name "Net-(U2-CT)") (class "Default")
      (node (ref "C6") (pin "2") (pinfunction "2_2") (pintype "passive"))
      (node (ref "U2") (pin "1") (pinfunction "CT_1") (pintype "passive"))
    )
    (net (code "60") (name "Net-(U2-MICBIAS)") (class "Default")
      (node (ref "R1") (pin "2") (pinfunction "2_2") (pintype "passive"))
      (node (ref "R6") (pin "1") (pinfunction "1_1") (pintype "passive"))
      (node (ref "U2") (pin "13") (pinfunction "MICBIAS_13") (pintype "passive"))
    )
    (net (code "61") (name "Net-(U2-MICIN)") (class "Default")
      (node (ref "C9") (pin "1") (pinfunction "1_1") (pintype "passive"))
      (node (ref "U2") (pin "8") (pinfunction "MICIN_8") (pintype "passive"))
    )
    (net (code "62") (name "Net-(U2-TH)") (class "Default")
      (node (ref "R6") (pin "2") (pinfunction "2_2") (pintype "passive"))
      (node (ref "R8") (pin "2") (pinfunction "2_2") (pintype "passive"))
      (node (ref "U2") (pin "14") (pinfunction "TH_14") (pintype "passive"))
    )
    (net (code "63") (name "Net-(U3-EN)") (class "Default")
      (node (ref "D5") (pin "C") (pinfunction "C_C") (pintype "passive"))
      (node (ref "D6") (pin "C") (pinfunction "C_C") (pintype "passive"))
      (node (ref "R4") (pin "1") (pinfunction "1_1") (pintype "passive"))
      (node (ref "U3") (pin "12") (pinfunction "EN_12") (pintype "passive"))
    )
    (net (code "64") (name "Net-(U3-FB)") (class "Default")
      (node (ref "R12") (pin "1") (pinfunction "1_1") (pintype "passive"))
      (node (ref "R9") (pin "2") (pinfunction "2_2") (pintype "passive"))
      (node (ref "U3") (pin "3") (pinfunction "FB_3") (pintype "passive"))
    )
    (net (code "65") (name "Net-(U3-VINA)") (class "Default")
      (node (ref "C28") (pin "2") (pinfunction "2_2") (pintype "passive"))
      (node (ref "U3") (pin "1") (pinfunction "VINA_1") (pintype "passive"))
    )
    (net (code "66") (name "Net-(U4-PROG)") (class "Default")
      (node (ref "R13") (pin "1") (pinfunction "1_1") (pintype "passive"))
      (node (ref "U4") (pin "6") (pinfunction "PROG_6") (pintype "passive"))
    )
    (net (code "67") (name "OLEDVPP") (class "Default")
      (node (ref "C11") (pin "1") (pinfunction "1_1") (pintype "passive"))
      (node (ref "C12") (pin "1") (pinfunction "1_1") (pintype "passive"))
      (node (ref "C7") (pin "1") (pinfunction "1_1") (pintype "passive"))
      (node (ref "D3") (pin "C") (pinfunction "C_C") (pintype "passive"))
      (node (ref "OLED") (pin "3") (pinfunction "3_3") (pintype "passive"))
      (node (ref "OLED") (pin "33") (pinfunction "33_33") (pintype "passive"))
      (node (ref "RB") (pin "1") (pinfunction "1_1") (pintype "passive"))
    )
    (net (code "68") (name "Power_EN") (class "Default")
      (node (ref "D5") (pin "A") (pinfunction "A_A") (pintype "passive"))
      (node (ref "U1") (pin "46") (pinfunction "PB9_46") (pintype "passive"))
    )
    (net (code "69") (name "unconnected-(CH340E-CTS#-Pad5)") (class "Default")
      (node (ref "CH340E") (pin "5") (pinfunction "CTS#_5") (pintype "passive"))
    )
    (net (code "70") (name "unconnected-(CH340E-RTS#-Pad4)") (class "Default")
      (node (ref "CH340E") (pin "4") (pinfunction "RTS#_4") (pintype "passive"))
    )
    (net (code "71") (name "unconnected-(CH340E-TNOW-Pad6)") (class "Default")
      (node (ref "CH340E") (pin "6") (pinfunction "TNOW_6") (pintype "passive"))
    )
    (net (code "72") (name "unconnected-(DS3231M-32kHZ-Pad1)") (class "Default")
      (node (ref "DS3231M") (pin "1") (pinfunction "32kHZ_1") (pintype "passive"))
    )
    (net (code "73") (name "unconnected-(DS3231M-RST-Pad4)") (class "Default")
      (node (ref "DS3231M") (pin "4") (pinfunction "RST_4") (pintype "passive"))
    )
    (net (code "74") (name "unconnected-(MT3608-NC-Pad6)") (class "Default")
      (node (ref "MT3608") (pin "6") (pinfunction "NC_6") (pintype "passive"))
    )
    (net (code "75") (name "unconnected-(OLED-Pad1)") (class "Default")
      (node (ref "OLED") (pin "1") (pinfunction "1_1") (pintype "passive+no_connect"))
    )
    (net (code "76") (name "unconnected-(OLED-Pad9)") (class "Default")
      (node (ref "OLED") (pin "9") (pinfunction "9_9") (pintype "passive+no_connect"))
    )
    (net (code "77") (name "unconnected-(OLED-Pad10)") (class "Default")
      (node (ref "OLED") (pin "10") (pinfunction "10_10") (pintype "passive"))
    )
    (net (code "78") (name "unconnected-(OLED-Pad11)") (class "Default")
      (node (ref "OLED") (pin "11") (pinfunction "11_11") (pintype "passive"))
    )
    (net (code "79") (name "unconnected-(OLED-Pad12)") (class "Default")
      (node (ref "OLED") (pin "12") (pinfunction "12_12") (pintype "passive"))
    )
    (net (code "80") (name "unconnected-(OLED-Pad13)") (class "Default")
      (node (ref "OLED") (pin "13") (pinfunction "13_13") (pintype "passive"))
    )
    (net (code "81") (name "unconnected-(OLED-Pad35)") (class "Default")
      (node (ref "OLED") (pin "35") (pinfunction "35_35") (pintype "passive+no_connect"))
    )
    (net (code "82") (name "unconnected-(U3-PG-Pad14)") (class "Default")
      (node (ref "U3") (pin "14") (pinfunction "PG_14") (pintype "passive"))
    )
    (net (code "83") (name "unconnected-(U4-STDBY-Pad5)") (class "Default")
      (node (ref "U4") (pin "5") (pinfunction "STDBY_5") (pintype "passive"))
    )
    (net (code "84") (name "unconnected-(USB-CC1-PadA5)") (class "Default")
      (node (ref "USB") (pin "A5") (pinfunction "CC1_A5") (pintype "passive"))
    )
    (net (code "85") (name "unconnected-(USB-CC2-PadB5)") (class "Default")
      (node (ref "USB") (pin "B5") (pinfunction "CC2_B5") (pintype "passive+no_connect"))
    )
    (net (code "86") (name "unconnected-(USB-RX1+-PadB11)") (class "Default")
      (node (ref "USB") (pin "B11") (pinfunction "RX1+_B11") (pintype "passive+no_connect"))
    )
    (net (code "87") (name "unconnected-(USB-RX1--PadB10)") (class "Default")
      (node (ref "USB") (pin "B10") (pinfunction "RX1-_B10") (pintype "passive+no_connect"))
    )
    (net (code "88") (name "unconnected-(USB-RX2+-PadA11)") (class "Default")
      (node (ref "USB") (pin "A11") (pinfunction "RX2+_A11") (pintype "passive+no_connect"))
    )
    (net (code "89") (name "unconnected-(USB-RX2--PadA10)") (class "Default")
      (node (ref "USB") (pin "A10") (pinfunction "RX2-_A10") (pintype "passive+no_connect"))
    )
    (net (code "90") (name "unconnected-(USB-SBU1-PadA8)") (class "Default")
      (node (ref "USB") (pin "A8") (pinfunction "SBU1_A8") (pintype "passive+no_connect"))
    )
    (net (code "91") (name "unconnected-(USB-SBU2-PadB8)") (class "Default")
      (node (ref "USB") (pin "B8") (pinfunction "SBU2_B8") (pintype "passive"))
    )
    (net (code "92") (name "unconnected-(USB-TX1+-PadA2)") (class "Default")
      (node (ref "USB") (pin "A2") (pinfunction "TX1+_A2") (pintype "passive+no_connect"))
    )
    (net (code "93") (name "unconnected-(USB-TX1--PadA3)") (class "Default")
      (node (ref "USB") (pin "A3") (pinfunction "TX1-_A3") (pintype "passive+no_connect"))
    )
    (net (code "94") (name "unconnected-(USB-TX2+-PadB2)") (class "Default")
      (node (ref "USB") (pin "B2") (pinfunction "TX2+_B2") (pintype "passive+no_connect"))
    )
    (net (code "95") (name "unconnected-(USB-TX2--PadB3)") (class "Default")
      (node (ref "USB") (pin "B3") (pinfunction "TX2-_B3") (pintype "passive+no_connect"))
    )
  )
)
